# Arduino_Nano_Clock_Divider_pcb2.net
KiCad netlist of a schematic drawn in EAGLE
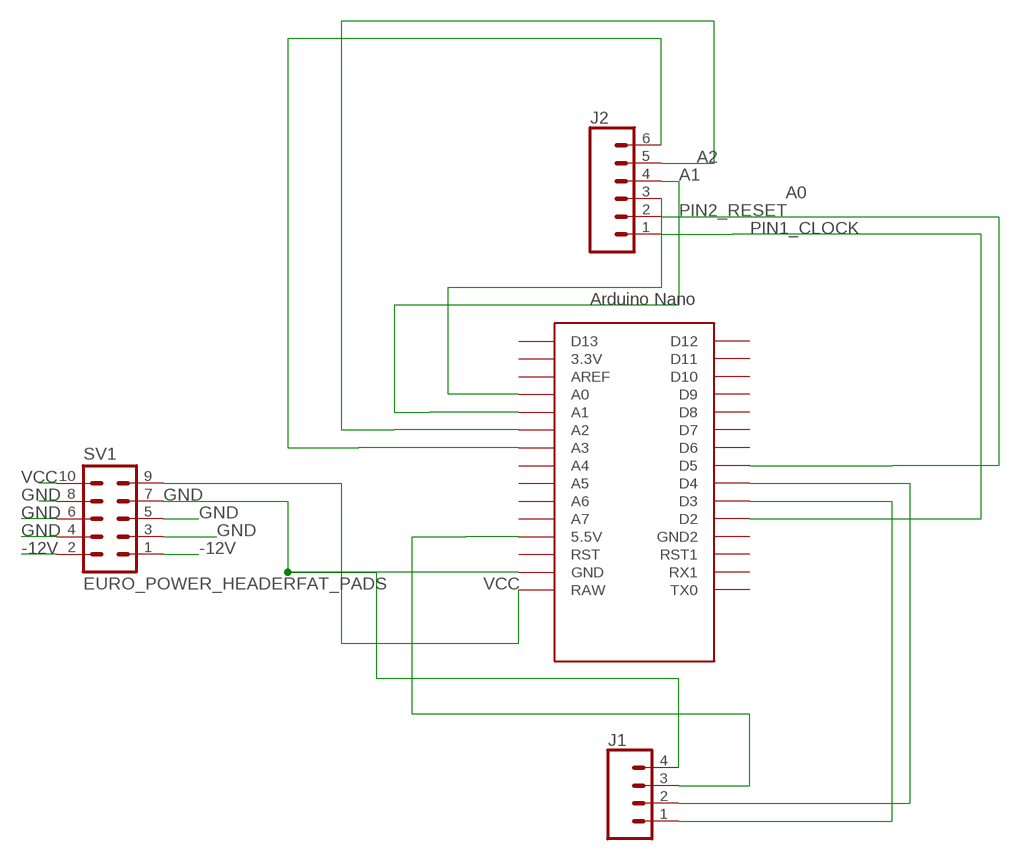
[diagram p0: schematic, sheet 1]

(export (version "E")
  (design (tool "Eeschema 10.0.6"))
  (components
    (comp (ref "J1")
      (value "CONN_04LONGPADS")
      (footprint "eagle-import:1X04_LONGPADS")
      (libsource (lib "eagle-import") (part "CONN_04LONGPADS"))
    )
    (comp (ref "J2")
      (value "CONN_06LONGPADS")
      (footprint "eagle-import:1X06_LONGPADS")
      (libsource (lib "eagle-import") (part "CONN_06LONGPADS"))
    )
    (comp (ref "SV1")
      (value "EURO_POWER_HEADERFAT_PADS")
      (footprint "eagle-import:EURO_PWR_HEADER_FAT")
      (libsource (lib "eagle-import") (part "EURO_POWER_HEADERFAT_PADS"))
    )
    (comp (ref "U$1")
      (value "NANO")
      (footprint "eagle-import:NANO")
      (libsource (lib "eagle-import") (part "NANO"))
    )
  )
  (nets
    (net (code "1") (name "/-12V") (class "Default")
      (node (ref "SV1") (pin "1") (pinfunction "1_1") (pintype "passive"))
      (node (ref "SV1") (pin "2") (pinfunction "2_2") (pintype "passive"))
    )
    (net (code "2") (name "/A0") (class "Default")
      (node (ref "J2") (pin "3") (pinfunction "3_3") (pintype "passive"))
      (node (ref "U$1") (pin "A0") (pinfunction "A0_A0") (pintype "bidirectional"))
    )
    (net (code "3") (name "/A1") (class "Default")
      (node (ref "J2") (pin "4") (pinfunction "4_4") (pintype "passive"))
      (node (ref "U$1") (pin "A1") (pinfunction "A1_A1") (pintype "bidirectional"))
    )
    (net (code "4") (name "/A2") (class "Default")
      (node (ref "J2") (pin "5") (pinfunction "5_5") (pintype "passive"))
      (node (ref "U$1") (pin "A2") (pinfunction "A2_A2") (pintype "bidirectional"))
    )
    (net (code "5") (name "/GND") (class "Default")
      (node (ref "J1") (pin "4") (pinfunction "4_4") (pintype "passive"))
      (node (ref "SV1") (pin "3") (pinfunction "3_3") (pintype "passive"))
      (node (ref "SV1") (pin "4") (pinfunction "4_4") (pintype "passive"))
      (node (ref "SV1") (pin "5") (pinfunction "5_5") (pintype "passive"))
      (node (ref "SV1") (pin "6") (pinfunction "6_6") (pintype "passive"))
      (node (ref "SV1") (pin "7") (pinfunction "7_7") (pintype "passive"))
      (node (ref "SV1") (pin "8") (pinfunction "8_8") (pintype "passive"))
      (node (ref "U$1") (pin "GND") (pinfunction "GND_GND") (pintype "bidirectional"))
    )
    (net (code "6") (name "/PIN1_CLOCK") (class "Default")
      (node (ref "J2") (pin "1") (pinfunction "1_1") (pintype "passive"))
      (node (ref "U$1") (pin "D2") (pinfunction "D2_D2") (pintype "bidirectional"))
    )
    (net (code "7") (name "/PIN2_RESET") (class "Default")
      (node (ref "J2") (pin "2") (pinfunction "2_2") (pintype "passive"))
      (node (ref "U$1") (pin "D5") (pinfunction "D5_D5") (pintype "bidirectional"))
    )
    (net (code "8") (name "/VCC") (class "Default")
      (node (ref "SV1") (pin "10") (pinfunction "10_10") (pintype "passive"))
      (node (ref "SV1") (pin "9") (pinfunction "9_9") (pintype "passive"))
      (node (ref "U$1") (pin "RAW") (pinfunction "RAW_RAW") (pintype "bidirectional"))
    )
    (net (code "9") (name "Net-(J1-Pad1)") (class "Default")
      (node (ref "J1") (pin "1") (pinfunction "1_1") (pintype "passive"))
      (node (ref "U$1") (pin "D3") (pinfunction "D3_D3") (pintype "bidirectional"))
    )
    (net (code "10") (name "Net-(J1-Pad2)") (class "Default")
      (node (ref "J1") (pin "2") (pinfunction "2_2") (pintype "passive"))
      (node (ref "U$1") (pin "D4") (pinfunction "D4_D4") (pintype "bidirectional"))
    )
    (net (code "11") (name "Net-(J2-Pad6)") (class "Default")
      (node (ref "J2") (pin "6") (pinfunction "6_6") (pintype "passive"))
      (node (ref "U$1") (pin "A3") (pinfunction "A3_A3") (pintype "bidirectional"))
    )
    (net (code "12") (name "Net-(U$1-5.5V)") (class "Default")
      (node (ref "J1") (pin "3") (pinfunction "3_3") (pintype "passive"))
      (node (ref "U$1") (pin "5V") (pinfunction "5.5V_5V") (pintype "bidirectional"))
    )
    (net (code "13") (name "unconnected-(U$1-GND2-PadGND1)") (class "Default")
      (node (ref "U$1") (pin "GND1") (pinfunction "GND2_GND1") (pintype "bidirectional"))
    )
    (net (code "14") (name "unconnected-(U$1-Pad3.3V)") (class "Default")
      (node (ref "U$1") (pin "3.3V") (pinfunction "3.3V_3.3V") (pintype "bidirectional"))
    )
    (net (code "15") (name "unconnected-(U$1-PadA4)") (class "Default")
      (node (ref "U$1") (pin "A4") (pinfunction "A4_A4") (pintype "bidirectional"))
    )
    (net (code "16") (name "unconnected-(U$1-PadA5)") (class "Default")
      (node (ref "U$1") (pin "A5") (pinfunction "A5_A5") (pintype "bidirectional"))
    )
    (net (code "17") (name "unconnected-(U$1-PadA6)") (class "Default")
      (node (ref "U$1") (pin "A6") (pinfunction "A6_A6") (pintype "bidirectional"))
    )
    (net (code "18") (name "unconnected-(U$1-PadA7)") (class "Default")
      (node (ref "U$1") (pin "A7") (pinfunction "A7_A7") (pintype "bidirectional"))
    )
    (net (code "19") (name "unconnected-(U$1-PadAREF)") (class "Default")
      (node (ref "U$1") (pin "AREF") (pinfunction "AREF_AREF") (pintype "bidirectional"))
    )
    (net (code "20") (name "unconnected-(U$1-PadD6)") (class "Default")
      (node (ref "U$1") (pin "D6") (pinfunction "D6_D6") (pintype "bidirectional"))
    )
    (net (code "21") (name "unconnected-(U$1-PadD7)") (class "Default")
      (node (ref "U$1") (pin "D7") (pinfunction "D7_D7") (pintype "bidirectional"))
    )
    (net (code "22") (name "unconnected-(U$1-PadD8)") (class "Default")
      (node (ref "U$1") (pin "D8") (pinfunction "D8_D8") (pintype "bidirectional"))
    )
    (net (code "23") (name "unconnected-(U$1-PadD9)") (class "Default")
      (node (ref "U$1") (pin "D9") (pinfunction "D9_D9") (pintype "bidirectional"))
    )
    (net (code "24") (name "unconnected-(U$1-PadD10)") (class "Default")
      (node (ref "U$1") (pin "D10") (pinfunction "D10_D10") (pintype "bidirectional"))
    )
    (net (code "25") (name "unconnected-(U$1-PadD11)") (class "Default")
      (node (ref "U$1") (pin "D11") (pinfunction "D11_D11") (pintype "bidirectional"))
    )
    (net (code "26") (name "unconnected-(U$1-PadD12)") (class "Default")
      (node (ref "U$1") (pin "D12") (pinfunction "D12_D12") (pintype "bidirectional"))
    )
    (net (code "27") (name "unconnected-(U$1-PadD13)") (class "Default")
      (node (ref "U$1") (pin "D13") (pinfunction "D13_D13") (pintype "bidirectional"))
    )
    (net (code "28") (name "unconnected-(U$1-PadICSP1)") (class "Default")
      (node (ref "U$1") (pin "ICSP1") (pinfunction "ICSP1_ICSP1") (pintype "bidirectional"))
    )
    (net (code "29") (name "unconnected-(U$1-PadICSP2)") (class "Default")
      (node (ref "U$1") (pin "ICSP2") (pinfunction "ICSP2_ICSP2") (pintype "bidirectional"))
    )
    (net (code "30") (name "unconnected-(U$1-PadICSP3)") (class "Default")
      (node (ref "U$1") (pin "ICSP3") (pinfunction "ICSP3_ICSP3") (pintype "bidirectional"))
    )
    (net (code "31") (name "unconnected-(U$1-PadICSP4)") (class "Default")
      (node (ref "U$1") (pin "ICSP4") (pinfunction "ICSP4_ICSP4") (pintype "bidirectional"))
    )
    (net (code "32") (name "unconnected-(U$1-PadICSP5)") (class "Default")
      (node (ref "U$1") (pin "ICSP5") (pinfunction "ICSP5_ICSP5") (pintype "bidirectional"))
    )
    (net (code "33") (name "unconnected-(U$1-PadICSP6)") (class "Default")
      (node (ref "U$1") (pin "ICSP6") (pinfunction "ICSP6_ICSP6") (pintype "bidirectional"))
    )
    (net (code "34") (name "unconnected-(U$1-PadRST)") (class "Default")
      (node (ref "U$1") (pin "RST") (pinfunction "RST_RST") (pintype "bidirectional"))
    )
    (net (code "35") (name "unconnected-(U$1-PadRST1)") (class "Default")
      (node (ref "U$1") (pin "RST1") (pinfunction "RST1_RST1") (pintype "bidirectional"))
    )
    (net (code "36") (name "unconnected-(U$1-PadRX1)") (class "Default")
      (node (ref "U$1") (pin "RX1") (pinfunction "RX1_RX1") (pintype "bidirectional"))
    )
    (net (code "37") (name "unconnected-(U$1-PadTX0)") (class "Default")
      (node (ref "U$1") (pin "TX0") (pinfunction "TX0_TX0") (pintype "bidirectional"))
    )
  )
)
